# bmp280_i2c.net
KiCad netlist of a schematic drawn in Altium Designer
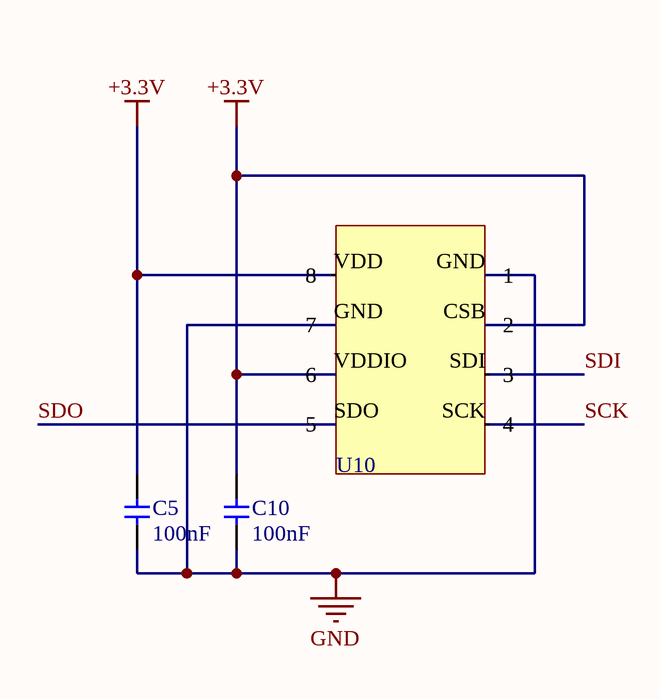
[diagram p0: bmp280_i2c.SchDoc]

(export (version "E")
  (design (tool "Eeschema 10.0.6"))
  (components
    (comp (ref "C5")
      (value "100nF")
      (footprint "0805")
      (description "Generic capacitor")
      (fields (field (name "Comment") "Generic Capacitor"))
      (libsource (lib "PowerCircuit") (part "Capacitor"))
    )
    (comp (ref "C10")
      (value "100nF")
      (footprint "0805")
      (description "Generic capacitor")
      (fields (field (name "Comment") "Generic Capacitor"))
      (libsource (lib "PowerCircuit") (part "Capacitor"))
    )
    (comp (ref "U10")
      (value "BMP280")
      (footprint "bmp280_i2c:bmp280_i2c")
      (libsource (lib "bmp280_i2c") (part "BMP280"))
    )
  )
  (nets
    (net (code "1") (name "+3.3V") (class "Default")
      (node (ref "C10") (pin "1") (pinfunction "1_1") (pintype "passive"))
      (node (ref "C5") (pin "1") (pinfunction "1_1") (pintype "passive"))
      (node (ref "U10") (pin "CSB") (pinfunction "2_CSB") (pintype "passive"))
      (node (ref "U10") (pin "VDD") (pinfunction "8_VDD") (pintype "passive"))
      (node (ref "U10") (pin "VDDIO") (pinfunction "6_VDDIO") (pintype "passive"))
    )
    (net (code "2") (name "/SCK") (class "Default")
      (node (ref "U10") (pin "SCK") (pinfunction "4_SCK") (pintype "passive"))
    )
    (net (code "3") (name "/SDI") (class "Default")
      (node (ref "U10") (pin "SDI") (pinfunction "3_SDI") (pintype "passive"))
    )
    (net (code "4") (name "/SDO") (class "Default")
      (node (ref "U10") (pin "SDO") (pinfunction "5_SDO") (pintype "passive"))
    )
    (net (code "5") (name "GND") (class "Default")
      (node (ref "C10") (pin "2") (pinfunction "2_2") (pintype "passive"))
      (node (ref "C5") (pin "2") (pinfunction "2_2") (pintype "passive"))
      (node (ref "U10") (pin "GND") (pinfunction "7_GND") (pintype "passive"))
    )
  )
)
